# Power.net
KiCad netlist of a schematic drawn in Altium Designer
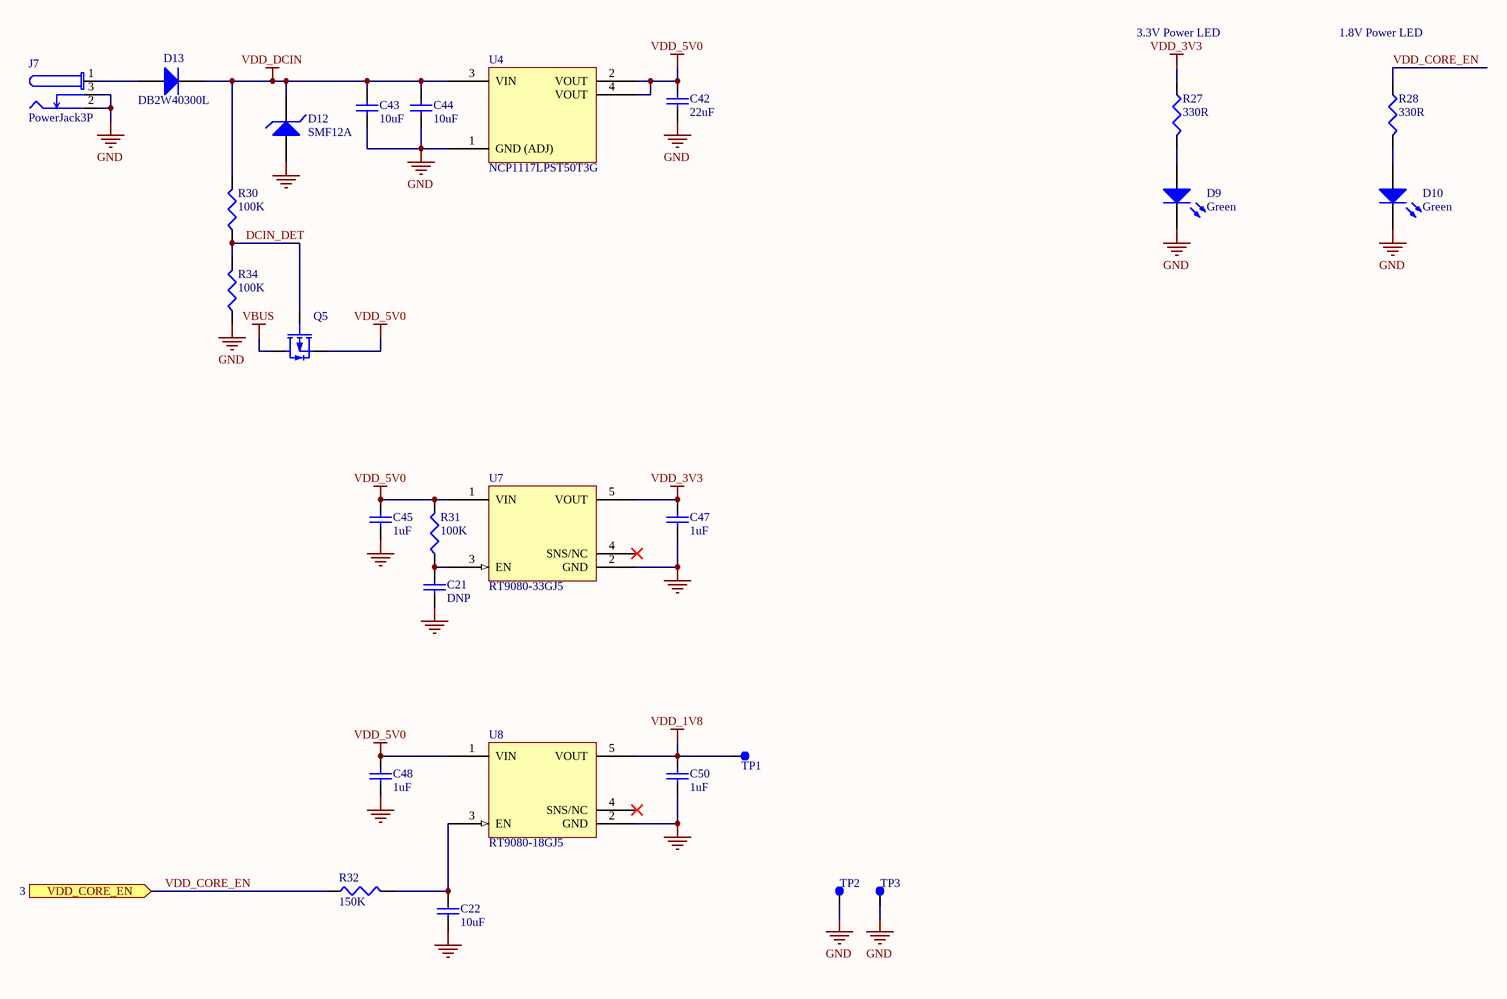
[diagram p0: Power.SchDoc]

(export (version "E")
  (design (tool "Eeschema 10.0.6"))
  (components
    (comp (ref "C21")
      (value "DNP")
      (footprint "C0603")
      (description "10µF 6.3V Ceramic Capacitor X5R 0603")
      (fields (field (name "PART NUMBER") "C0100007") (field (name "MANUFACTURER") "Murata Electronics"))
      (libsource (lib "PartLibrary") (part "Capacitor - non polarized"))
    )
    (comp (ref "C22")
      (value "10uF")
      (footprint "C0603")
      (description "CAP CER 10UF 10V X5R 0603")
      (fields (field (name "PART NUMBER") "C0100033") (field (name "MANUFACTURER") "Murata Electronics"))
      (libsource (lib "PartLibrary") (part "Capacitor - non polarized"))
    )
    (comp (ref "C42")
      (value "22uF")
      (footprint "C0805")
      (description "22µF 6.3V Ceramic Capacitor X5R 0805")
      (fields (field (name "PART NUMBER") "C0100010") (field (name "MANUFACTURER") "Murata Electronics"))
      (libsource (lib "PartLibrary") (part "Capacitor - non polarized"))
    )
    (comp (ref "C43")
      (value "10uF")
      (footprint "C0805")
      (description "10µF ±10% 25V Ceramic Capacitor X5R 0805")
      (fields (field (name "PART NUMBER") "C0100015") (field (name "MANUFACTURER") "Murata Electronics"))
      (libsource (lib "PartLibrary") (part "Capacitor - non polarized"))
    )
    (comp (ref "C44")
      (value "10uF")
      (footprint "C0805")
      (description "10µF ±10% 25V Ceramic Capacitor X5R 0805")
      (fields (field (name "PART NUMBER") "C0100015") (field (name "MANUFACTURER") "Murata Electronics"))
      (libsource (lib "PartLibrary") (part "Capacitor - non polarized"))
    )
    (comp (ref "C45")
      (value "1uF")
      (footprint "C0603")
      (description "1µF 16V Ceramic Capacitor X5R 0603")
      (fields (field (name "PART NUMBER") "C0100006") (field (name "MANUFACTURER") "Murata Electronics"))
      (libsource (lib "PartLibrary") (part "Capacitor - non polarized"))
    )
    (comp (ref "C47")
      (value "1uF")
      (footprint "C0603")
      (description "1µF 16V Ceramic Capacitor X5R 0603")
      (fields (field (name "PART NUMBER") "C0100006") (field (name "MANUFACTURER") "Murata Electronics"))
      (libsource (lib "PartLibrary") (part "Capacitor - non polarized"))
    )
    (comp (ref "C48")
      (value "1uF")
      (footprint "C0603")
      (description "1µF 16V Ceramic Capacitor X5R 0603")
      (fields (field (name "PART NUMBER") "C0100006") (field (name "MANUFACTURER") "Murata Electronics"))
      (libsource (lib "PartLibrary") (part "Capacitor - non polarized"))
    )
    (comp (ref "C50")
      (value "1uF")
      (footprint "C0603")
      (description "1µF 16V Ceramic Capacitor X5R 0603")
      (fields (field (name "PART NUMBER") "C0100006") (field (name "MANUFACTURER") "Murata Electronics"))
      (libsource (lib "PartLibrary") (part "Capacitor - non polarized"))
    )
    (comp (ref "D9")
      (value "Green")
      (footprint "LED0805")
      (description "Green 570nm LED Indication - Discrete 2.2V 0805")
      (fields
        (field (name "PART NUMBER") "E0000001")
        (field (name "MANUFACTURER") "OSRAM Opto Semiconductors Inc")
      )
      (libsource (lib "PartLibrary") (part "LED"))
    )
    (comp (ref "D10")
      (value "Green")
      (footprint "LED0805")
      (description "Green 570nm LED Indication - Discrete 2.2V 0805")
      (fields
        (field (name "PART NUMBER") "E0000001")
        (field (name "MANUFACTURER") "OSRAM Opto Semiconductors Inc")
      )
      (libsource (lib "PartLibrary") (part "LED"))
    )
    (comp (ref "D12")
      (value "SMF12A")
      (footprint "SOD-123FL")
      (description "TVS DIODE 12VWM 19.9VC SOD123")
      (fields (field (name "PART NUMBER") "D0000002") (field (name "MANUFACTURER") "Littelfuse Inc"))
      (libsource (lib "PartLibrary") (part "Diode Zener"))
    )
    (comp (ref "D13")
      (value "DB2W40300L")
      (footprint "SOD-123FL")
      (description "Diode Schottky 40V 3A (DC) Surface Mount")
      (fields
        (field (name "PART NUMBER") "D0000006")
        (field (name "MANUFACTURER") "Panasonic Electronic Components")
      )
      (libsource (lib "PartLibrary") (part "Diode"))
    )
    (comp (ref "J7")
      (value "PowerJack3P")
      (footprint "PJ-102AH")
      (description "Power Barrel Connector Jack 2.00mm ID (0.079\"), 5.50mm OD (0.217\") Through Hole, Right Angle")
      (fields (field (name "PART NUMBER") "J0000003") (field (name "MANUFACTURER") "CUI Inc"))
      (libsource (lib "PartLibrary") (part "PowerJack3P"))
    )
    (comp (ref "Q5")
      (value "MOSFET-P_SOT23")
      (footprint "SOT-23B")
      (description "MOSFET P-CH 20V 4.2A SOT23")
      (fields (field (name "PART NUMBER") "Q0000005") (field (name "MANUFACTURER") "Diodes Inc"))
      (libsource (lib "PartLibrary") (part "MOSFET-P_SOT23"))
    )
    (comp (ref "R27")
      (value "330R")
      (footprint "R0402")
      (description "RES SMD 330 OHM 1% 1/16W 0402")
      (fields (field (name "PART NUMBER") "R0000026") (field (name "MANUFACTURER") "Yageo"))
      (libsource (lib "PartLibrary") (part "Resistor"))
    )
    (comp (ref "R28")
      (value "330R")
      (footprint "R0402")
      (description "RES SMD 330 OHM 1% 1/16W 0402")
      (fields (field (name "PART NUMBER") "R0000026") (field (name "MANUFACTURER") "Yageo"))
      (libsource (lib "PartLibrary") (part "Resistor"))
    )
    (comp (ref "R30")
      (value "100K")
      (footprint "R0402")
      (description "RES SMD 100K OHM 1% 1/16W 0402")
      (fields (field (name "PART NUMBER") "R0000012") (field (name "MANUFACTURER") "Yageo"))
      (libsource (lib "PartLibrary") (part "Resistor"))
    )
    (comp (ref "R31")
      (value "100K")
      (footprint "R0402")
      (description "RES SMD 100K OHM 1% 1/16W 0402")
      (fields (field (name "PART NUMBER") "R0000012") (field (name "MANUFACTURER") "Yageo"))
      (libsource (lib "PartLibrary") (part "Resistor"))
    )
    (comp (ref "R32")
      (value "150K")
      (footprint "R0402")
      (description "RES SMD 150K OHM 1% 1/16W 0402")
      (fields (field (name "PART NUMBER") "R0000055") (field (name "MANUFACTURER") "Yageo"))
      (libsource (lib "PartLibrary") (part "Resistor"))
    )
    (comp (ref "R34")
      (value "100K")
      (footprint "R0402")
      (description "RES SMD 100K OHM 1% 1/16W 0402")
      (fields (field (name "PART NUMBER") "R0000012") (field (name "MANUFACTURER") "Yageo"))
      (libsource (lib "PartLibrary") (part "Resistor"))
    )
    (comp (ref "TP1")
      (value "Testpoint")
      (footprint "Testpoint_SMT")
      (description "Test Point SMT")
      (fields (field (name "PART NUMBER") "M0000002"))
      (libsource (lib "PartLibrary") (part "Testpoint"))
    )
    (comp (ref "TP2")
      (value "Testpoint")
      (footprint "Testpoint_SMT")
      (description "Test Point SMT")
      (fields (field (name "PART NUMBER") "M0000002"))
      (libsource (lib "PartLibrary") (part "Testpoint"))
    )
    (comp (ref "TP3")
      (value "Testpoint")
      (footprint "Testpoint_SMT")
      (description "Test Point SMT")
      (fields (field (name "PART NUMBER") "M0000002"))
      (libsource (lib "PartLibrary") (part "Testpoint"))
    )
    (comp (ref "U4")
      (value "NCP1117LPST50T3G")
      (footprint "SOT223P700X180-4N")
      (description "IC REG LINEAR 5V 1A SOT223")
      (fields (field (name "PART NUMBER") "U0000051") (field (name "MANUFACTURER") "ON Semiconductor"))
      (libsource (lib "PartLibrary") (part "NCP1117"))
    )
    (comp (ref "U7")
      (value "RT9080-33GJ5")
      (footprint "TSOT23-5")
      (description "Linear Voltage Regulator IC Positive Fixed 1 Output 3.3V 600mA TSOT-23-5")
      (fields (field (name "PART NUMBER") "U0000066") (field (name "MANUFACTURER") "Richtek USA"))
      (libsource (lib "PartLibrary") (part "RT9080-TSOT"))
    )
    (comp (ref "U8")
      (value "RT9080-18GJ5")
      (footprint "TSOT23-5")
      (description "Linear Voltage Regulator IC Positive Fixed 1 Output 1.8V 600mA TSOT-23-5")
      (fields (field (name "PART NUMBER") "U0000065") (field (name "MANUFACTURER") "Richtek USA"))
      (libsource (lib "PartLibrary") (part "RT9080-TSOT"))
    )
  )
  (nets
    (net (code "1") (name "/DCIN_DET") (class "Default")
      (node (ref "Q5") (pin "1") (pinfunction "G_1") (pintype "passive"))
      (node (ref "R30") (pin "1") (pinfunction "1_1") (pintype "passive"))
      (node (ref "R34") (pin "2") (pinfunction "2_2") (pintype "passive"))
    )
    (net (code "2") (name "/VDD_CORE_EN") (class "Default")
      (node (ref "R28") (pin "1") (pinfunction "1_1") (pintype "passive"))
      (node (ref "R32") (pin "1") (pinfunction "1_1") (pintype "passive"))
    )
    (net (code "3") (name "GND") (class "Default")
      (node (ref "C21") (pin "2") (pinfunction "2_2") (pintype "passive"))
      (node (ref "C22") (pin "2") (pinfunction "2_2") (pintype "passive"))
      (node (ref "C42") (pin "2") (pinfunction "2_2") (pintype "passive"))
      (node (ref "C43") (pin "2") (pinfunction "2_2") (pintype "passive"))
      (node (ref "C44") (pin "2") (pinfunction "2_2") (pintype "passive"))
      (node (ref "C45") (pin "2") (pinfunction "2_2") (pintype "passive"))
      (node (ref "C47") (pin "2") (pinfunction "2_2") (pintype "passive"))
      (node (ref "C48") (pin "2") (pinfunction "2_2") (pintype "passive"))
      (node (ref "C50") (pin "2") (pinfunction "2_2") (pintype "passive"))
      (node (ref "D10") (pin "1") (pinfunction "K_1") (pintype "passive"))
      (node (ref "D12") (pin "2") (pinfunction "A_2") (pintype "passive"))
      (node (ref "D9") (pin "1") (pinfunction "K_1") (pintype "passive"))
      (node (ref "J7") (pin "2") (pinfunction "2_2") (pintype "power_in"))
      (node (ref "J7") (pin "3") (pinfunction "3_3") (pintype "power_in"))
      (node (ref "R34") (pin "1") (pinfunction "1_1") (pintype "passive"))
      (node (ref "TP2") (pin "1") (pinfunction "1_1") (pintype "passive"))
      (node (ref "TP3") (pin "1") (pinfunction "1_1") (pintype "passive"))
      (node (ref "U4") (pin "1") (pinfunction "GND_(ADJ)_1") (pintype "passive"))
      (node (ref "U7") (pin "2") (pinfunction "GND_2") (pintype "passive"))
      (node (ref "U8") (pin "2") (pinfunction "GND_2") (pintype "passive"))
    )
    (net (code "4") (name "Net-(D9-A)") (class "Default")
      (node (ref "D9") (pin "2") (pinfunction "A_2") (pintype "passive"))
      (node (ref "R27") (pin "2") (pinfunction "2_2") (pintype "passive"))
    )
    (net (code "5") (name "Net-(D10-A)") (class "Default")
      (node (ref "D10") (pin "2") (pinfunction "A_2") (pintype "passive"))
      (node (ref "R28") (pin "2") (pinfunction "2_2") (pintype "passive"))
    )
    (net (code "6") (name "Net-(D13-A)") (class "Default")
      (node (ref "D13") (pin "2") (pinfunction "A_2") (pintype "passive"))
      (node (ref "J7") (pin "1") (pinfunction "1_1") (pintype "power_in"))
    )
    (net (code "7") (name "Net-(U7-EN)") (class "Default")
      (node (ref "C21") (pin "1") (pinfunction "1_1") (pintype "passive"))
      (node (ref "R31") (pin "1") (pinfunction "1_1") (pintype "passive"))
      (node (ref "U7") (pin "3") (pinfunction "EN_3") (pintype "input"))
    )
    (net (code "8") (name "Net-(U8-EN)") (class "Default")
      (node (ref "C22") (pin "1") (pinfunction "1_1") (pintype "passive"))
      (node (ref "R32") (pin "2") (pinfunction "2_2") (pintype "passive"))
      (node (ref "U8") (pin "3") (pinfunction "EN_3") (pintype "input"))
    )
    (net (code "9") (name "VBUS") (class "Default")
      (node (ref "Q5") (pin "3") (pinfunction "D_3") (pintype "passive"))
    )
    (net (code "10") (name "VDD_1V8") (class "Default")
      (node (ref "C50") (pin "1") (pinfunction "1_1") (pintype "passive"))
      (node (ref "TP1") (pin "1") (pinfunction "1_1") (pintype "passive"))
      (node (ref "U8") (pin "5") (pinfunction "VOUT_5") (pintype "power_in"))
    )
    (net (code "11") (name "VDD_3V3") (class "Default")
      (node (ref "C47") (pin "1") (pinfunction "1_1") (pintype "passive"))
      (node (ref "R27") (pin "1") (pinfunction "1_1") (pintype "passive"))
      (node (ref "U7") (pin "5") (pinfunction "VOUT_5") (pintype "power_in"))
    )
    (net (code "12") (name "VDD_5V0") (class "Default")
      (node (ref "C42") (pin "1") (pinfunction "1_1") (pintype "passive"))
      (node (ref "C45") (pin "1") (pinfunction "1_1") (pintype "passive"))
      (node (ref "C48") (pin "1") (pinfunction "1_1") (pintype "passive"))
      (node (ref "Q5") (pin "2") (pinfunction "S_2") (pintype "passive"))
      (node (ref "R31") (pin "2") (pinfunction "2_2") (pintype "passive"))
      (node (ref "U4") (pin "2") (pinfunction "VOUT_2") (pintype "power_in"))
      (node (ref "U4") (pin "4") (pinfunction "VOUT_4") (pintype "power_in"))
      (node (ref "U7") (pin "1") (pinfunction "VIN_1") (pintype "power_in"))
      (node (ref "U8") (pin "1") (pinfunction "VIN_1") (pintype "power_in"))
    )
    (net (code "13") (name "VDD_DCIN") (class "Default")
      (node (ref "C43") (pin "1") (pinfunction "1_1") (pintype "passive"))
      (node (ref "C44") (pin "1") (pinfunction "1_1") (pintype "passive"))
      (node (ref "D12") (pin "1") (pinfunction "K_1") (pintype "passive"))
      (node (ref "D13") (pin "1") (pinfunction "K_1") (pintype "passive"))
      (node (ref "R30") (pin "2") (pinfunction "2_2") (pintype "passive"))
      (node (ref "U4") (pin "3") (pinfunction "VIN_3") (pintype "power_in"))
    )
    (net (code "14") (name "unconnected-(U7-SNS{slash}NC-Pad4)") (class "Default")
      (node (ref "U7") (pin "4") (pinfunction "SNS/NC_4") (pintype "passive+no_connect"))
    )
    (net (code "15") (name "unconnected-(U8-SNS{slash}NC-Pad4)") (class "Default")
      (node (ref "U8") (pin "4") (pinfunction "SNS/NC_4") (pintype "passive+no_connect"))
    )
  )
)
